# myUZE_final.net
KiCad netlist of a schematic drawn in EAGLE
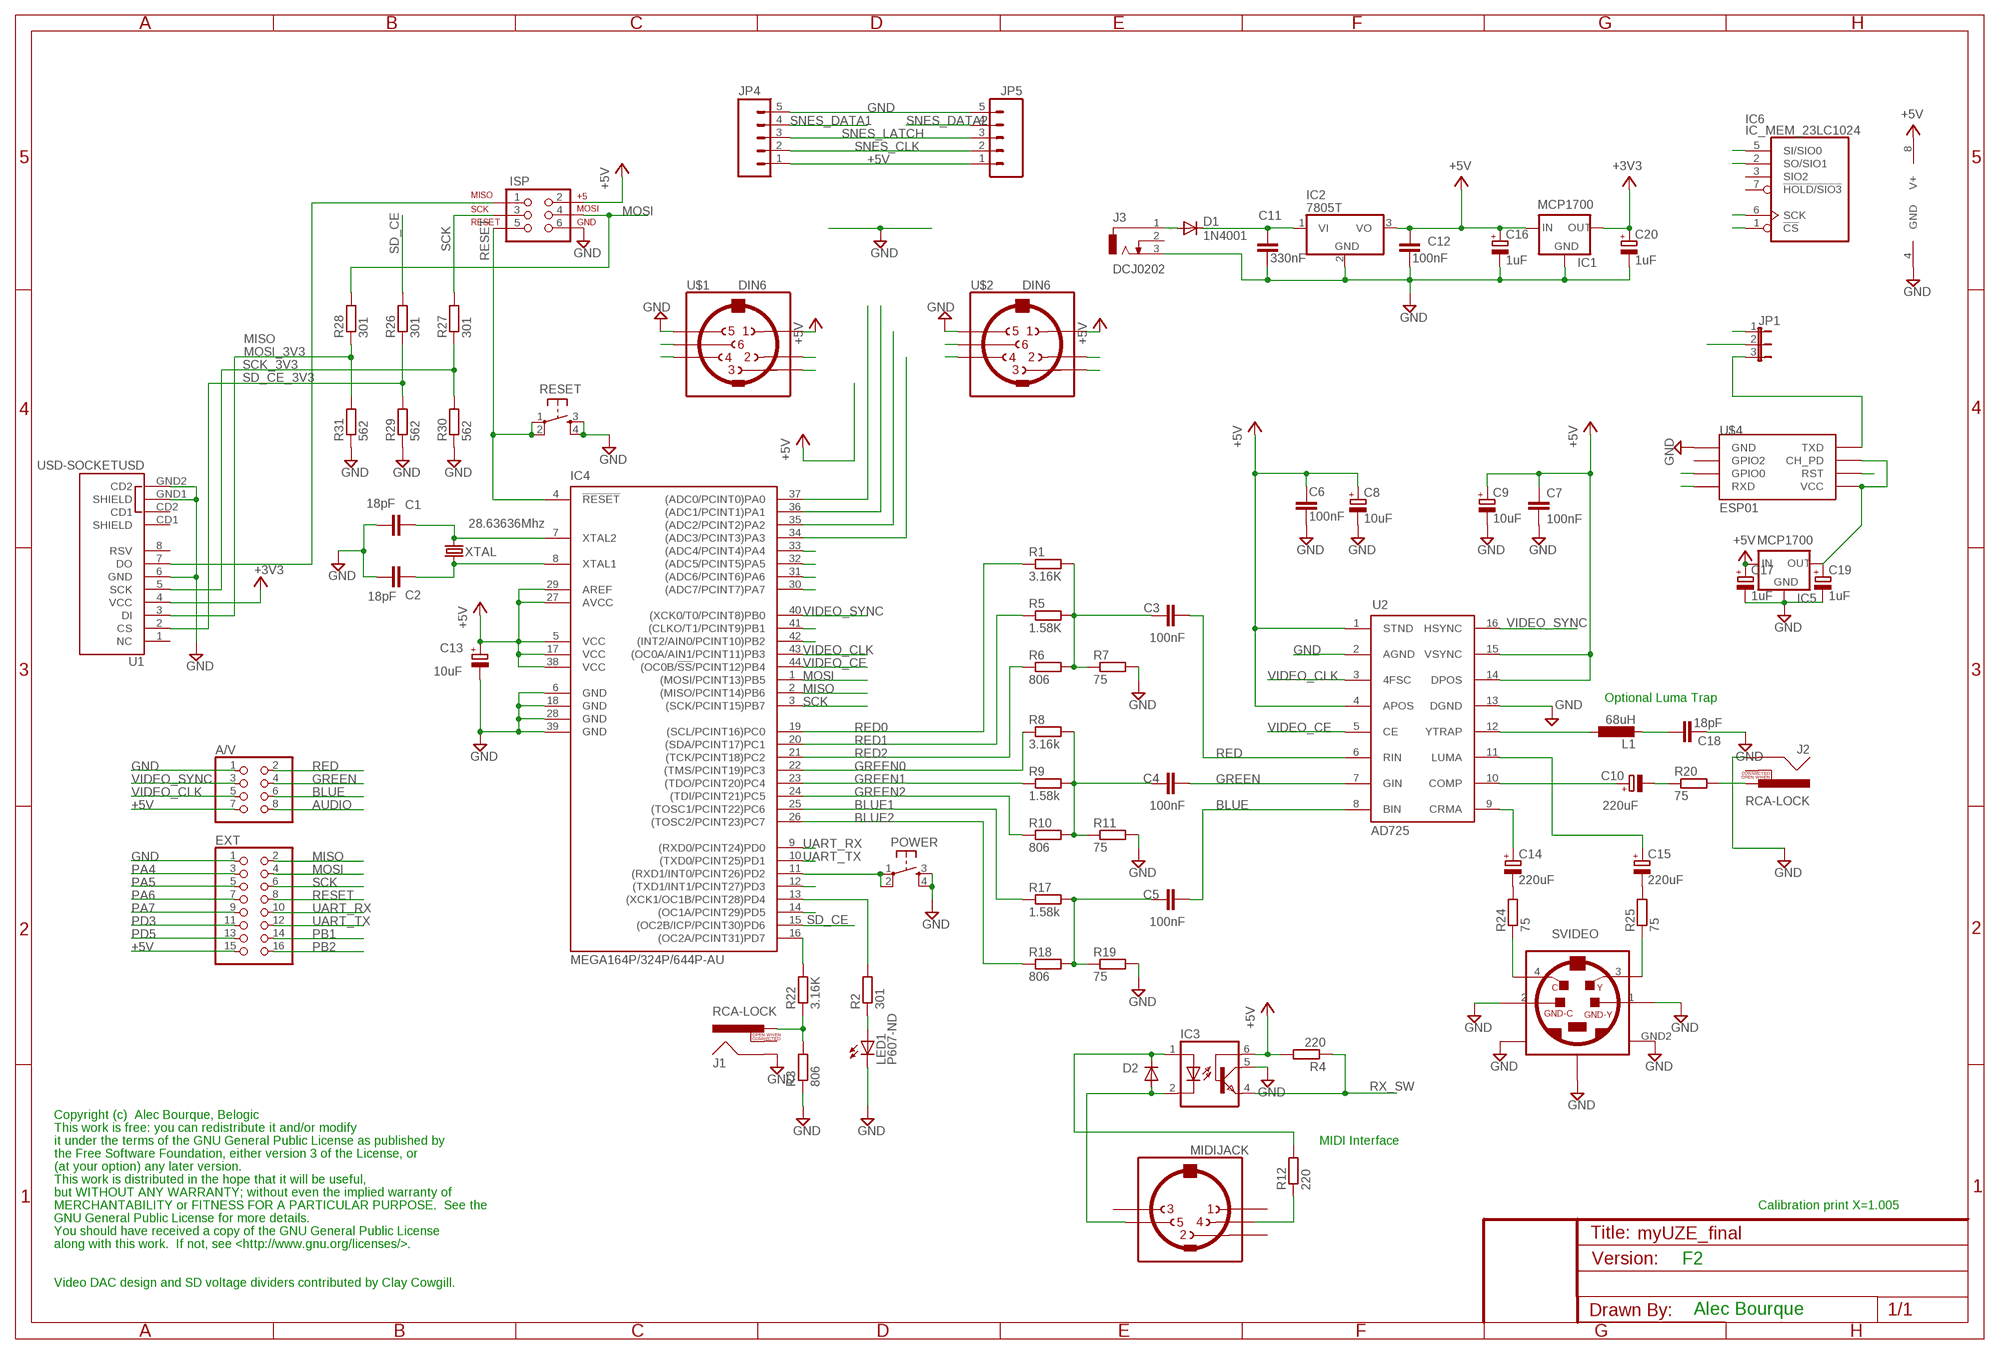
[diagram p0: schematic, sheet 1]

(export (version "E")
  (design (tool "Eeschema 10.0.6"))
  (components
    (comp (ref "A/V")
      (value "PINHD-2X4")
      (footprint "eagle-import:2X04")
      (libsource (lib "eagle-import") (part "PINHD-2X4"))
    )
    (comp (ref "AD725")
      (value "AD725")
      (footprint "eagle-import:SO16W")
      (fields (field (name "IC_NO") "U2") (field (name "NAME") "AD725"))
      (libsource (lib "eagle-import") (part "AD725"))
    )
    (comp (ref "C1")
      (value "18pF")
      (footprint "eagle-import:C0805")
      (libsource (lib "eagle-import") (part "C-EUC0805"))
    )
    (comp (ref "C2")
      (value "18pF")
      (footprint "eagle-import:C0805")
      (libsource (lib "eagle-import") (part "C-EUC0805"))
    )
    (comp (ref "C3")
      (value "100nF")
      (footprint "eagle-import:C0805")
      (libsource (lib "eagle-import") (part "C-EUC0805"))
    )
    (comp (ref "C4")
      (value "100nF")
      (footprint "eagle-import:C0805")
      (libsource (lib "eagle-import") (part "C-EUC0805"))
    )
    (comp (ref "C5")
      (value "100nF")
      (footprint "eagle-import:C0805")
      (libsource (lib "eagle-import") (part "C-EUC0805"))
    )
    (comp (ref "C6")
      (value "100nF")
      (footprint "eagle-import:C0805")
      (libsource (lib "eagle-import") (part "C-EUC0805"))
    )
    (comp (ref "C7")
      (value "100nF")
      (footprint "eagle-import:C0805")
      (libsource (lib "eagle-import") (part "C-EUC0805"))
    )
    (comp (ref "C8")
      (value "10uF")
      (footprint "eagle-import:153CLV-0505")
      (libsource (lib "eagle-import") (part "CPOL-EU153CLV-0505"))
    )
    (comp (ref "C9")
      (value "10uF")
      (footprint "eagle-import:153CLV-0505")
      (libsource (lib "eagle-import") (part "CPOL-EU153CLV-0505"))
    )
    (comp (ref "C10")
      (value "220uF")
      (footprint "eagle-import:E2-5")
      (libsource (lib "eagle-import") (part "CPOL-EUE2-5"))
    )
    (comp (ref "C11")
      (value "330nF")
      (footprint "eagle-import:C0805")
      (libsource (lib "eagle-import") (part "C-EUC0805"))
    )
    (comp (ref "C12")
      (value "100nF")
      (footprint "eagle-import:C0805")
      (libsource (lib "eagle-import") (part "C-EUC0805"))
    )
    (comp (ref "C13")
      (value "10uF")
      (footprint "eagle-import:153CLV-0505")
      (libsource (lib "eagle-import") (part "CPOL-EU153CLV-0505"))
    )
    (comp (ref "C14")
      (value "220uF")
      (footprint "eagle-import:E2-5")
      (libsource (lib "eagle-import") (part "CPOL-EUE2-5"))
    )
    (comp (ref "C15")
      (value "220uF")
      (footprint "eagle-import:E2-5")
      (libsource (lib "eagle-import") (part "CPOL-EUE2-5"))
    )
    (comp (ref "C16")
      (value "1uF")
      (footprint "eagle-import:153CLV-0505")
      (libsource (lib "eagle-import") (part "CPOL-EU153CLV-0505"))
    )
    (comp (ref "C17")
      (value "1uF")
      (footprint "eagle-import:153CLV-0505")
      (libsource (lib "eagle-import") (part "CPOL-EU153CLV-0505"))
    )
    (comp (ref "C18")
      (value "18pF")
      (footprint "eagle-import:C0805")
      (libsource (lib "eagle-import") (part "C-EUC0805"))
    )
    (comp (ref "C19")
      (value "1uF")
      (footprint "eagle-import:153CLV-0505")
      (libsource (lib "eagle-import") (part "CPOL-EU153CLV-0505"))
    )
    (comp (ref "C20")
      (value "1uF")
      (footprint "eagle-import:153CLV-0505")
      (libsource (lib "eagle-import") (part "CPOL-EU153CLV-0505"))
    )
    (comp (ref "D1")
      (value "1N4001")
      (footprint "eagle-import:MELF-MLL41")
      (libsource (lib "eagle-import") (part "DIODE-MELF-MLL41"))
    )
    (comp (ref "D2")
      (value "DIODE-MINIMELF")
      (footprint "eagle-import:MINIMELF")
      (libsource (lib "eagle-import") (part "DIODE-MINIMELF"))
    )
    (comp (ref "EXT")
      (value "PINHD-2X8")
      (footprint "eagle-import:2X08")
      (libsource (lib "eagle-import") (part "PINHD-2X8"))
    )
    (comp (ref "IC1")
      (value "MCP1700")
      (footprint "eagle-import:TO92-INLINE")
      (libsource (lib "eagle-import") (part "MCP1700INLINE"))
    )
    (comp (ref "IC2")
      (value "7805T")
      (footprint "eagle-import:TO220H")
      (libsource (lib "eagle-import") (part "78T05"))
    )
    (comp (ref "IC3")
      (value "PC110")
      (footprint "eagle-import:DIL06")
      (libsource (lib "eagle-import") (part "PC110"))
    )
    (comp (ref "IC4")
      (value "MEGA164P/324P/644P-AU")
      (footprint "eagle-import:TQFP44")
      (libsource (lib "eagle-import") (part "MEGA164P/324P/644P-AU"))
    )
    (comp (ref "IC5")
      (value "MCP1700")
      (footprint "eagle-import:TO92-INLINE")
      (libsource (lib "eagle-import") (part "MCP1700INLINE"))
    )
    (comp (ref "IC6")
      (value "IC_MEM_23LC1024")
      (footprint "eagle-import:SOIC-8")
      (libsource (lib "eagle-import") (part "IC_MEM_23LC1024"))
    )
    (comp (ref "ISP")
      (value "AVR_SPI_PRG_6PTH")
      (footprint "eagle-import:2X3")
      (libsource (lib "eagle-import") (part "AVR_SPI_PRG_6PTH"))
    )
    (comp (ref "J1")
      (value "RCA-LOCK")
      (footprint "eagle-import:RCA_LOCK")
      (libsource (lib "eagle-import") (part "RCA-LOCK"))
    )
    (comp (ref "J2")
      (value "RCA-LOCK")
      (footprint "eagle-import:RCA_LOCK")
      (libsource (lib "eagle-import") (part "RCA-LOCK"))
    )
    (comp (ref "J3")
      (value "DCJ0202")
      (footprint "eagle-import:DCJ0202")
      (libsource (lib "eagle-import") (part "DCJ0202"))
    )
    (comp (ref "JP1")
      (value "JP2E")
      (footprint "eagle-import:JP2")
      (libsource (lib "eagle-import") (part "JP2E"))
    )
    (comp (ref "JP4")
      (value "M05PTH")
      (footprint "eagle-import:1X05")
      (libsource (lib "eagle-import") (part "M05PTH"))
    )
    (comp (ref "JP5")
      (value "M05PTH")
      (footprint "eagle-import:1X05")
      (libsource (lib "eagle-import") (part "M05PTH"))
    )
    (comp (ref "L1")
      (value "68uH")
      (footprint "eagle-import:IR-4")
      (libsource (lib "eagle-import") (part "L-EUIR-4"))
    )
    (comp (ref "LED1")
      (value "P607-ND")
      (footprint "eagle-import:Q62902-B155")
      (libsource (lib "eagle-import") (part "LEDB155"))
    )
    (comp (ref "POWER")
      (value "USER")
      (footprint "eagle-import:TACTILE-PTH")
      (libsource (lib "eagle-import") (part "TAC_SWITCHPTH"))
    )
    (comp (ref "R1")
      (value "3.16K")
      (footprint "eagle-import:R0805")
      (libsource (lib "eagle-import") (part "R-EU_R0805"))
    )
    (comp (ref "R2")
      (value "301")
      (footprint "eagle-import:R0805")
      (libsource (lib "eagle-import") (part "R-EU_R0805"))
    )
    (comp (ref "R3")
      (value "806")
      (footprint "eagle-import:R0805")
      (libsource (lib "eagle-import") (part "R-EU_R0805"))
    )
    (comp (ref "R4")
      (value "220")
      (footprint "eagle-import:R0805")
      (libsource (lib "eagle-import") (part "R-EU_R0805"))
    )
    (comp (ref "R5")
      (value "1.58K")
      (footprint "eagle-import:R0805")
      (libsource (lib "eagle-import") (part "R-EU_R0805"))
    )
    (comp (ref "R6")
      (value "806")
      (footprint "eagle-import:R0805")
      (libsource (lib "eagle-import") (part "R-EU_R0805"))
    )
    (comp (ref "R7")
      (value "75")
      (footprint "eagle-import:R0805")
      (libsource (lib "eagle-import") (part "R-EU_R0805"))
    )
    (comp (ref "R8")
      (value "3.16k")
      (footprint "eagle-import:R0805")
      (libsource (lib "eagle-import") (part "R-EU_R0805"))
    )
    (comp (ref "R9")
      (value "1.58k")
      (footprint "eagle-import:R0805")
      (libsource (lib "eagle-import") (part "R-EU_R0805"))
    )
    (comp (ref "R10")
      (value "806")
      (footprint "eagle-import:R0805")
      (libsource (lib "eagle-import") (part "R-EU_R0805"))
    )
    (comp (ref "R11")
      (value "75")
      (footprint "eagle-import:R0805")
      (libsource (lib "eagle-import") (part "R-EU_R0805"))
    )
    (comp (ref "R12")
      (value "220")
      (footprint "eagle-import:R0805")
      (libsource (lib "eagle-import") (part "R-EU_R0805"))
    )
    (comp (ref "R17")
      (value "1.58k")
      (footprint "eagle-import:R0805")
      (libsource (lib "eagle-import") (part "R-EU_R0805"))
    )
    (comp (ref "R18")
      (value "806")
      (footprint "eagle-import:R0805")
      (libsource (lib "eagle-import") (part "R-EU_R0805"))
    )
    (comp (ref "R19")
      (value "75")
      (footprint "eagle-import:R0805")
      (libsource (lib "eagle-import") (part "R-EU_R0805"))
    )
    (comp (ref "R20")
      (value "75")
      (footprint "eagle-import:R0805")
      (libsource (lib "eagle-import") (part "R-EU_R0805"))
    )
    (comp (ref "R22")
      (value "3.16K")
      (footprint "eagle-import:R0805")
      (libsource (lib "eagle-import") (part "R-EU_R0805"))
    )
    (comp (ref "R24")
      (value "75")
      (footprint "eagle-import:R0805")
      (libsource (lib "eagle-import") (part "R-EU_R0805"))
    )
    (comp (ref "R25")
      (value "75")
      (footprint "eagle-import:R0805")
      (libsource (lib "eagle-import") (part "R-EU_R0805"))
    )
    (comp (ref "R26")
      (value "301")
      (footprint "eagle-import:R0805")
      (libsource (lib "eagle-import") (part "R-EU_R0805"))
    )
    (comp (ref "R27")
      (value "301")
      (footprint "eagle-import:R0805")
      (libsource (lib "eagle-import") (part "R-EU_R0805"))
    )
    (comp (ref "R28")
      (value "301")
      (footprint "eagle-import:R0805")
      (libsource (lib "eagle-import") (part "R-EU_R0805"))
    )
    (comp (ref "R29")
      (value "562")
      (footprint "eagle-import:R0805")
      (libsource (lib "eagle-import") (part "R-EU_R0805"))
    )
    (comp (ref "R30")
      (value "562")
      (footprint "eagle-import:R0805")
      (libsource (lib "eagle-import") (part "R-EU_R0805"))
    )
    (comp (ref "R31")
      (value "562")
      (footprint "eagle-import:R0805")
      (libsource (lib "eagle-import") (part "R-EU_R0805"))
    )
    (comp (ref "RESET")
      (value "RESET")
      (footprint "eagle-import:TACTILE-PTH")
      (libsource (lib "eagle-import") (part "TAC_SWITCHPTH"))
    )
    (comp (ref "SVIDEO")
      (value "S-VIDEO OUT")
      (footprint "eagle-import:MINIDIN4")
      (libsource (lib "eagle-import") (part "MINIDIN"))
    )
    (comp (ref "U$1")
      (value "DIN6")
      (footprint "eagle-import:DIN6")
      (libsource (lib "eagle-import") (part "DIN6"))
    )
    (comp (ref "U$2")
      (value "DIN6")
      (footprint "eagle-import:DIN6")
      (libsource (lib "eagle-import") (part "DIN6"))
    )
    (comp (ref "U$4")
      (value "ESP01")
      (footprint "eagle-import:ESP01")
      (libsource (lib "eagle-import") (part "ESP01"))
    )
    (comp (ref "U$5")
      (value "MIDIJACK")
      (footprint "eagle-import:CP-2350")
      (libsource (lib "eagle-import") (part "MIDIJACK"))
    )
    (comp (ref "U1")
      (value "USD-SOCKETUSD")
      (footprint "eagle-import:USD-SOCKET-PP")
      (libsource (lib "eagle-import") (part "USD-SOCKETUSD"))
    )
    (comp (ref "XTAL")
      (value "28.63636Mhz")
      (footprint "eagle-import:HC49_S")
      (libsource (lib "eagle-import") (part "CRYSTALHC49S"))
    )
  )
  (nets
    (net (code "1") (name "+3V3") (class "Default")
      (node (ref "C20") (pin "+") (pinfunction "+_+") (pintype "passive"))
      (node (ref "IC1") (pin "3") (pinfunction "OUT_3") (pintype "passive"))
      (node (ref "U1") (pin "4") (pinfunction "VCC_4") (pintype "bidirectional"))
    )
    (net (code "2") (name "+5V") (class "Default")
      (node (ref "A/V") (pin "7") (pinfunction "7_7") (pintype "passive"))
      (node (ref "AD725") (pin "1") (pinfunction "STND_1") (pintype "input"))
      (node (ref "AD725") (pin "14") (pinfunction "DPOS_14") (pintype "power_in"))
      (node (ref "AD725") (pin "15") (pinfunction "VSYNC_15") (pintype "input"))
      (node (ref "AD725") (pin "4") (pinfunction "APOS_4") (pintype "power_in"))
      (node (ref "C12") (pin "1") (pinfunction "1_1") (pintype "passive"))
      (node (ref "C13") (pin "+") (pinfunction "+_+") (pintype "passive"))
      (node (ref "C16") (pin "+") (pinfunction "+_+") (pintype "passive"))
      (node (ref "C17") (pin "+") (pinfunction "+_+") (pintype "passive"))
      (node (ref "C6") (pin "1") (pinfunction "1_1") (pintype "passive"))
      (node (ref "C7") (pin "1") (pinfunction "1_1") (pintype "passive"))
      (node (ref "C8") (pin "+") (pinfunction "+_+") (pintype "passive"))
      (node (ref "C9") (pin "+") (pinfunction "+_+") (pintype "passive"))
      (node (ref "EXT") (pin "15") (pinfunction "15_15") (pintype "passive"))
      (node (ref "IC1") (pin "2") (pinfunction "IN_2") (pintype "input"))
      (node (ref "IC2") (pin "3") (pinfunction "VO_3") (pintype "passive"))
      (node (ref "IC3") (pin "6") (pinfunction "BAS_6") (pintype "passive"))
      (node (ref "IC4") (pin "17") (pinfunction "VCC_17") (pintype "power_in"))
      (node (ref "IC4") (pin "27") (pinfunction "AVCC_27") (pintype "power_in"))
      (node (ref "IC4") (pin "29") (pinfunction "AREF_29") (pintype "power_in"))
      (node (ref "IC4") (pin "38") (pinfunction "VCC_38") (pintype "power_in"))
      (node (ref "IC4") (pin "5") (pinfunction "VCC_5") (pintype "power_in"))
      (node (ref "IC5") (pin "2") (pinfunction "IN_2") (pintype "input"))
      (node (ref "IC6") (pin "8") (pinfunction "V+_8") (pintype "power_in"))
      (node (ref "ISP") (pin "2") (pinfunction "2_2") (pintype "passive"))
      (node (ref "JP4") (pin "1") (pinfunction "1_1") (pintype "passive"))
      (node (ref "JP5") (pin "1") (pinfunction "1_1") (pintype "passive"))
      (node (ref "R4") (pin "2") (pinfunction "2_2") (pintype "passive"))
      (node (ref "U$1") (pin "P1") (pinfunction "P1_P1") (pintype "passive"))
      (node (ref "U$2") (pin "P1") (pinfunction "P1_P1") (pintype "passive"))
    )
    (net (code "3") (name "/AUDIO") (class "Default")
      (node (ref "A/V") (pin "8") (pinfunction "8_8") (pintype "passive"))
      (node (ref "J1") (pin "PIN") (pinfunction "PIN_PIN") (pintype "bidirectional"))
      (node (ref "R22") (pin "1") (pinfunction "1_1") (pintype "passive"))
      (node (ref "R3") (pin "2") (pinfunction "2_2") (pintype "passive"))
    )
    (net (code "4") (name "/BLUE") (class "Default")
      (node (ref "A/V") (pin "6") (pinfunction "6_6") (pintype "passive"))
      (node (ref "AD725") (pin "8") (pinfunction "BIN_8") (pintype "input"))
      (node (ref "C5") (pin "2") (pinfunction "2_2") (pintype "passive"))
    )
    (net (code "5") (name "/BLUE1") (class "Default")
      (node (ref "IC4") (pin "25") (pinfunction "(TOSC1/PCINT22)PC6_25") (pintype "bidirectional"))
      (node (ref "R17") (pin "1") (pinfunction "1_1") (pintype "passive"))
    )
    (net (code "6") (name "/BLUE2") (class "Default")
      (node (ref "IC4") (pin "26") (pinfunction "(TOSC2/PCINT23)PC7_26") (pintype "bidirectional"))
      (node (ref "R18") (pin "1") (pinfunction "1_1") (pintype "passive"))
    )
    (net (code "7") (name "/GREEN") (class "Default")
      (node (ref "A/V") (pin "4") (pinfunction "4_4") (pintype "passive"))
      (node (ref "AD725") (pin "7") (pinfunction "GIN_7") (pintype "input"))
      (node (ref "C4") (pin "2") (pinfunction "2_2") (pintype "passive"))
    )
    (net (code "8") (name "/GREEN0") (class "Default")
      (node (ref "IC4") (pin "22") (pinfunction "(TMS/PCINT19)PC3_22") (pintype "bidirectional"))
      (node (ref "R8") (pin "1") (pinfunction "1_1") (pintype "passive"))
    )
    (net (code "9") (name "/GREEN1") (class "Default")
      (node (ref "IC4") (pin "23") (pinfunction "(TDO/PCINT20)PC4_23") (pintype "bidirectional"))
      (node (ref "R9") (pin "1") (pinfunction "1_1") (pintype "passive"))
    )
    (net (code "10") (name "/GREEN2") (class "Default")
      (node (ref "IC4") (pin "24") (pinfunction "(TDI/PCINT21)PC5_24") (pintype "bidirectional"))
      (node (ref "R10") (pin "1") (pinfunction "1_1") (pintype "passive"))
    )
    (net (code "11") (name "/MISO") (class "Default")
      (node (ref "EXT") (pin "2") (pinfunction "2_2") (pintype "passive"))
      (node (ref "IC4") (pin "2") (pinfunction "(MISO/PCINT14)PB6_2") (pintype "bidirectional"))
      (node (ref "IC6") (pin "2") (pinfunction "SO/SIO1_2") (pintype "bidirectional"))
      (node (ref "ISP") (pin "1") (pinfunction "1_1") (pintype "passive"))
      (node (ref "U1") (pin "7") (pinfunction "DO_7") (pintype "bidirectional"))
    )
    (net (code "12") (name "/MOSI") (class "Default")
      (node (ref "EXT") (pin "4") (pinfunction "4_4") (pintype "passive"))
      (node (ref "IC4") (pin "1") (pinfunction "(MOSI/PCINT13)PB5_1") (pintype "bidirectional"))
      (node (ref "IC6") (pin "5") (pinfunction "SI/SIO0_5") (pintype "bidirectional"))
      (node (ref "ISP") (pin "4") (pinfunction "4_4") (pintype "passive"))
      (node (ref "R28") (pin "2") (pinfunction "2_2") (pintype "passive"))
    )
    (net (code "13") (name "/MOSI_3V3") (class "Default")
      (node (ref "R28") (pin "1") (pinfunction "1_1") (pintype "passive"))
      (node (ref "R31") (pin "2") (pinfunction "2_2") (pintype "passive"))
      (node (ref "U1") (pin "3") (pinfunction "DI_3") (pintype "bidirectional"))
    )
    (net (code "14") (name "/PA4") (class "Default")
      (node (ref "EXT") (pin "3") (pinfunction "3_3") (pintype "passive"))
      (node (ref "IC4") (pin "33") (pinfunction "(ADC4/PCINT4)PA4_33") (pintype "bidirectional"))
      (node (ref "IC6") (pin "1") (pinfunction "~{CS}_1") (pintype "input"))
    )
    (net (code "15") (name "/PA5") (class "Default")
      (node (ref "EXT") (pin "5") (pinfunction "5_5") (pintype "passive"))
      (node (ref "IC4") (pin "32") (pinfunction "(ADC5/PCINT5)PA5_32") (pintype "bidirectional"))
    )
    (net (code "16") (name "/PA6") (class "Default")
      (node (ref "EXT") (pin "7") (pinfunction "7_7") (pintype "passive"))
      (node (ref "IC4") (pin "31") (pinfunction "(ADC6/PCINT6)PA6_31") (pintype "bidirectional"))
    )
    (net (code "17") (name "/PA7") (class "Default")
      (node (ref "EXT") (pin "9") (pinfunction "9_9") (pintype "passive"))
      (node (ref "IC4") (pin "30") (pinfunction "(ADC7/PCINT7)PA7_30") (pintype "bidirectional"))
      (node (ref "U$4") (pin "GPIO0") (pinfunction "GPIO0_GPIO0") (pintype "bidirectional"))
    )
    (net (code "18") (name "/PB1") (class "Default")
      (node (ref "EXT") (pin "14") (pinfunction "14_14") (pintype "passive"))
      (node (ref "IC4") (pin "41") (pinfunction "(CLKO/T1/PCINT9)PB1_41") (pintype "bidirectional"))
    )
    (net (code "19") (name "/PB2") (class "Default")
      (node (ref "EXT") (pin "16") (pinfunction "16_16") (pintype "passive"))
      (node (ref "IC4") (pin "42") (pinfunction "(INT2/AIN0/PCINT10)PB2_42") (pintype "bidirectional"))
    )
    (net (code "20") (name "/PD3") (class "Default")
      (node (ref "EXT") (pin "11") (pinfunction "11_11") (pintype "passive"))
      (node (ref "IC4") (pin "12") (pinfunction "(TXD1/INT1/PCINT27)PD3_12") (pintype "bidirectional"))
      (node (ref "U$4") (pin "RST") (pinfunction "RST_RST") (pintype "bidirectional"))
    )
    (net (code "21") (name "/PD5") (class "Default")
      (node (ref "EXT") (pin "13") (pinfunction "13_13") (pintype "passive"))
      (node (ref "IC4") (pin "14") (pinfunction "(OC1A/PCINT29)PD5_14") (pintype "bidirectional"))
    )
    (net (code "22") (name "/RED") (class "Default")
      (node (ref "A/V") (pin "2") (pinfunction "2_2") (pintype "passive"))
      (node (ref "AD725") (pin "6") (pinfunction "RIN_6") (pintype "input"))
      (node (ref "C3") (pin "2") (pinfunction "2_2") (pintype "passive"))
    )
    (net (code "23") (name "/RED0") (class "Default")
      (node (ref "IC4") (pin "19") (pinfunction "(SCL/PCINT16)PC0_19") (pintype "bidirectional"))
      (node (ref "R1") (pin "1") (pinfunction "1_1") (pintype "passive"))
    )
    (net (code "24") (name "/RED1") (class "Default")
      (node (ref "IC4") (pin "20") (pinfunction "(SDA/PCINT17)PC1_20") (pintype "bidirectional"))
      (node (ref "R5") (pin "1") (pinfunction "1_1") (pintype "passive"))
    )
    (net (code "25") (name "/RED2") (class "Default")
      (node (ref "IC4") (pin "21") (pinfunction "(TCK/PCINT18)PC2_21") (pintype "bidirectional"))
      (node (ref "R6") (pin "1") (pinfunction "1_1") (pintype "passive"))
    )
    (net (code "26") (name "/RESET") (class "Default")
      (node (ref "EXT") (pin "8") (pinfunction "8_8") (pintype "passive"))
      (node (ref "IC4") (pin "4") (pinfunction "~{RESET}_4") (pintype "input"))
      (node (ref "ISP") (pin "5") (pinfunction "5_5") (pintype "passive"))
      (node (ref "RESET") (pin "1") (pinfunction "1_1") (pintype "passive"))
      (node (ref "RESET") (pin "2") (pinfunction "2_2") (pintype "passive"))
    )
    (net (code "27") (name "/RX_SW") (class "Default")
      (node (ref "IC3") (pin "4") (pinfunction "EMI_4") (pintype "passive"))
      (node (ref "JP1") (pin "1") (pinfunction "1_1") (pintype "passive"))
      (node (ref "R4") (pin "1") (pinfunction "1_1") (pintype "passive"))
    )
    (net (code "28") (name "/SCK") (class "Default")
      (node (ref "EXT") (pin "6") (pinfunction "6_6") (pintype "passive"))
      (node (ref "IC4") (pin "3") (pinfunction "(SCK/PCINT15)PB7_3") (pintype "bidirectional"))
      (node (ref "IC6") (pin "6") (pinfunction "SCK_6") (pintype "input"))
      (node (ref "ISP") (pin "3") (pinfunction "3_3") (pintype "passive"))
      (node (ref "R27") (pin "2") (pinfunction "2_2") (pintype "passive"))
    )
    (net (code "29") (name "/SCK_3V3") (class "Default")
      (node (ref "R27") (pin "1") (pinfunction "1_1") (pintype "passive"))
      (node (ref "R30") (pin "2") (pinfunction "2_2") (pintype "passive"))
      (node (ref "U1") (pin "5") (pinfunction "SCK_5") (pintype "bidirectional"))
    )
    (net (code "30") (name "/SD_CE") (class "Default")
      (node (ref "IC4") (pin "15") (pinfunction "(OC2B/ICP/PCINT30)PD6_15") (pintype "bidirectional"))
      (node (ref "R26") (pin "2") (pinfunction "2_2") (pintype "passive"))
    )
    (net (code "31") (name "/SD_CE_3V3") (class "Default")
      (node (ref "R26") (pin "1") (pinfunction "1_1") (pintype "passive"))
      (node (ref "R29") (pin "2") (pinfunction "2_2") (pintype "passive"))
      (node (ref "U1") (pin "2") (pinfunction "CS_2") (pintype "bidirectional"))
    )
    (net (code "32") (name "/SNES_CLK") (class "Default")
      (node (ref "IC4") (pin "34") (pinfunction "(ADC3/PCINT3)PA3_34") (pintype "bidirectional"))
      (node (ref "JP4") (pin "2") (pinfunction "2_2") (pintype "passive"))
      (node (ref "JP5") (pin "2") (pinfunction "2_2") (pintype "passive"))
      (node (ref "U$1") (pin "P2") (pinfunction "P2_P2") (pintype "passive"))
      (node (ref "U$2") (pin "P2") (pinfunction "P2_P2") (pintype "passive"))
    )
    (net (code "33") (name "/SNES_DATA1") (class "Default")
      (node (ref "IC4") (pin "37") (pinfunction "(ADC0/PCINT0)PA0_37") (pintype "bidirectional"))
      (node (ref "JP4") (pin "4") (pinfunction "4_4") (pintype "passive"))
      (node (ref "U$2") (pin "P4") (pinfunction "P4_P4") (pintype "passive"))
    )
    (net (code "34") (name "/SNES_DATA2") (class "Default")
      (node (ref "IC4") (pin "36") (pinfunction "(ADC1/PCINT1)PA1_36") (pintype "bidirectional"))
      (node (ref "JP5") (pin "4") (pinfunction "4_4") (pintype "passive"))
      (node (ref "U$1") (pin "P4") (pinfunction "P4_P4") (pintype "passive"))
    )
    (net (code "35") (name "/SNES_LATCH") (class "Default")
      (node (ref "IC4") (pin "35") (pinfunction "(ADC2/PCINT2)PA2_35") (pintype "bidirectional"))
      (node (ref "JP4") (pin "3") (pinfunction "3_3") (pintype "passive"))
      (node (ref "JP5") (pin "3") (pinfunction "3_3") (pintype "passive"))
      (node (ref "U$1") (pin "P3") (pinfunction "P3_P3") (pintype "passive"))
      (node (ref "U$2") (pin "P3") (pinfunction "P3_P3") (pintype "passive"))
    )
    (net (code "36") (name "/UART_RX") (class "Default")
      (node (ref "EXT") (pin "10") (pinfunction "10_10") (pintype "passive"))
      (node (ref "IC4") (pin "9") (pinfunction "(RXD0/PCINT24)PD0_9") (pintype "bidirectional"))
      (node (ref "JP1") (pin "2") (pinfunction "2_2") (pintype "passive"))
    )
    (net (code "37") (name "/UART_TX") (class "Default")
      (node (ref "EXT") (pin "12") (pinfunction "12_12") (pintype "passive"))
      (node (ref "IC4") (pin "10") (pinfunction "(TXD0/PCINT25)PD1_10") (pintype "bidirectional"))
      (node (ref "U$4") (pin "RX") (pinfunction "RXD_RX") (pintype "bidirectional"))
    )
    (net (code "38") (name "/VIDEO_CE") (class "Default")
      (node (ref "AD725") (pin "5") (pinfunction "CE_5") (pintype "input"))
      (node (ref "IC4") (pin "44") (pinfunction "(OC0B/~{SS}/PCINT12)PB4_44") (pintype "bidirectional"))
    )
    (net (code "39") (name "/VIDEO_CLK") (class "Default")
      (node (ref "A/V") (pin "5") (pinfunction "5_5") (pintype "passive"))
      (node (ref "AD725") (pin "3") (pinfunction "4FSC_3") (pintype "input"))
      (node (ref "IC4") (pin "43") (pinfunction "(OC0A/AIN1/PCINT11)PB3_43") (pintype "bidirectional"))
    )
    (net (code "40") (name "/VIDEO_SYNC") (class "Default")
      (node (ref "A/V") (pin "3") (pinfunction "3_3") (pintype "passive"))
      (node (ref "AD725") (pin "16") (pinfunction "HSYNC_16") (pintype "input"))
      (node (ref "IC4") (pin "40") (pinfunction "(XCK0/T0/PCINT8)PB0_40") (pintype "bidirectional"))
    )
    (net (code "41") (name "GND") (class "Default")
      (node (ref "A/V") (pin "1") (pinfunction "1_1") (pintype "passive"))
      (node (ref "AD725") (pin "13") (pinfunction "DGND_13") (pintype "passive"))
      (node (ref "AD725") (pin "2") (pinfunction "AGND_2") (pintype "passive"))
      (node (ref "C1") (pin "2") (pinfunction "2_2") (pintype "passive"))
      (node (ref "C11") (pin "2") (pinfunction "2_2") (pintype "passive"))
      (node (ref "C12") (pin "2") (pinfunction "2_2") (pintype "passive"))
      (node (ref "C13") (pin "-") (pinfunction "-_-") (pintype "passive"))
      (node (ref "C16") (pin "-") (pinfunction "-_-") (pintype "passive"))
      (node (ref "C17") (pin "-") (pinfunction "-_-") (pintype "passive"))
      (node (ref "C18") (pin "2") (pinfunction "2_2") (pintype "passive"))
      (node (ref "C19") (pin "-") (pinfunction "-_-") (pintype "passive"))
      (node (ref "C2") (pin "2") (pinfunction "2_2") (pintype "passive"))
      (node (ref "C20") (pin "-") (pinfunction "-_-") (pintype "passive"))
      (node (ref "C6") (pin "2") (pinfunction "2_2") (pintype "passive"))
      (node (ref "C7") (pin "2") (pinfunction "2_2") (pintype "passive"))
      (node (ref "C8") (pin "-") (pinfunction "-_-") (pintype "passive"))
      (node (ref "C9") (pin "-") (pinfunction "-_-") (pintype "passive"))
      (node (ref "EXT") (pin "1") (pinfunction "1_1") (pintype "passive"))
      (node (ref "IC1") (pin "1") (pinfunction "GND_1") (pintype "input"))
      (node (ref "IC2") (pin "2") (pinfunction "GND_2") (pintype "passive"))
      (node (ref "IC3") (pin "5") (pinfunction "COL_5") (pintype "passive"))
      (node (ref "IC4") (pin "18") (pinfunction "GND_18") (pintype "power_in"))
      (node (ref "IC4") (pin "28") (pinfunction "GND_28") (pintype "power_in"))
      (node (ref "IC4") (pin "39") (pinfunction "GND_39") (pintype "power_in"))
      (node (ref "IC4") (pin "6") (pinfunction "GND_6") (pintype "power_in"))
      (node (ref "IC5") (pin "1") (pinfunction "GND_1") (pintype "input"))
      (node (ref "IC6") (pin "4") (pinfunction "GND_4") (pintype "power_in"))
      (node (ref "ISP") (pin "6") (pinfunction "6_6") (pintype "passive"))
      (node (ref "J1") (pin "SHELL") (pinfunction "SHELL_SHELL") (pintype "bidirectional"))
      (node (ref "J2") (pin "SHELL") (pinfunction "SHELL_SHELL") (pintype "bidirectional"))
      (node (ref "J3") (pin "3") (pinfunction "3_3") (pintype "passive"))
      (node (ref "JP4") (pin "5") (pinfunction "5_5") (pintype "passive"))
      (node (ref "JP5") (pin "5") (pinfunction "5_5") (pintype "passive"))
      (node (ref "LED1") (pin "K") (pinfunction "C_K") (pintype "passive"))
      (node (ref "POWER") (pin "3") (pinfunction "3_3") (pintype "passive"))
      (node (ref "POWER") (pin "4") (pinfunction "4_4") (pintype "passive"))
      (node (ref "R11") (pin "2") (pinfunction "2_2") (pintype "passive"))
      (node (ref "R19") (pin "2") (pinfunction "2_2") (pintype "passive"))
      (node (ref "R29") (pin "1") (pinfunction "1_1") (pintype "passive"))
      (node (ref "R3") (pin "1") (pinfunction "1_1") (pintype "passive"))
      (node (ref "R30") (pin "1") (pinfunction "1_1") (pintype "passive"))
      (node (ref "R31") (pin "1") (pinfunction "1_1") (pintype "passive"))
      (node (ref "R7") (pin "2") (pinfunction "2_2") (pintype "passive"))
      (node (ref "RESET") (pin "3") (pinfunction "3_3") (pintype "passive"))
      (node (ref "RESET") (pin "4") (pinfunction "4_4") (pintype "passive"))
      (node (ref "SVIDEO") (pin "1") (pinfunction "GND-Y_1") (pintype "passive"))
      (node (ref "SVIDEO") (pin "2") (pinfunction "GND-C_2") (pintype "passive"))
      (node (ref "SVIDEO") (pin "GND1") (pinfunction "P$5_GND1") (pintype "passive"))
      (node (ref "SVIDEO") (pin "GND2") (pinfunction "P$6_GND2") (pintype "passive"))
      (node (ref "SVIDEO") (pin "GND3") (pinfunction "P$7_GND3") (pintype "passive"))
      (node (ref "U$1") (pin "P5") (pinfunction "P5_P5") (pintype "passive"))
      (node (ref "U$2") (pin "P5") (pinfunction "P5_P5") (pintype "passive"))
      (node (ref "U$4") (pin "GND") (pinfunction "GND_GND") (pintype "bidirectional"))
      (node (ref "U1") (pin "6") (pinfunction "GND_6") (pintype "bidirectional"))
      (node (ref "U1") (pin "GND1") (pinfunction "SHIELD_GND1") (pintype "bidirectional"))
      (node (ref "U1") (pin "GND2") (pinfunction "CD2_GND2") (pintype "bidirectional"))
    )
    (net (code "42") (name "Net-(AD725-COMP)") (class "Default")
      (node (ref "AD725") (pin "10") (pinfunction "COMP_10") (pintype "output"))
      (node (ref "C10") (pin "+") (pinfunction "+_+") (pintype "passive"))
    )
    (net (code "43") (name "Net-(AD725-CRMA)") (class "Default")
      (node (ref "AD725") (pin "9") (pinfunction "CRMA_9") (pintype "output"))
      (node (ref "C14") (pin "+") (pinfunction "+_+") (pintype "passive"))
    )
    (net (code "44") (name "Net-(AD725-LUMA)") (class "Default")
      (node (ref "AD725") (pin "11") (pinfunction "LUMA_11") (pintype "output"))
      (node (ref "C15") (pin "+") (pinfunction "+_+") (pintype "passive"))
    )
    (net (code "45") (name "Net-(AD725-YTRAP)") (class "Default")
      (node (ref "AD725") (pin "12") (pinfunction "YTRAP_12") (pintype "output"))
      (node (ref "L1") (pin "1") (pinfunction "1_1") (pintype "passive"))
    )
    (net (code "46") (name "Net-(C3-Pad1)") (class "Default")
      (node (ref "C3") (pin "1") (pinfunction "1_1") (pintype "passive"))
      (node (ref "R1") (pin "2") (pinfunction "2_2") (pintype "passive"))
      (node (ref "R5") (pin "2") (pinfunction "2_2") (pintype "passive"))
      (node (ref "R6") (pin "2") (pinfunction "2_2") (pintype "passive"))
      (node (ref "R7") (pin "1") (pinfunction "1_1") (pintype "passive"))
    )
    (net (code "47") (name "Net-(C4-Pad1)") (class "Default")
      (node (ref "C4") (pin "1") (pinfunction "1_1") (pintype "passive"))
      (node (ref "R10") (pin "2") (pinfunction "2_2") (pintype "passive"))
      (node (ref "R11") (pin "1") (pinfunction "1_1") (pintype "passive"))
      (node (ref "R8") (pin "2") (pinfunction "2_2") (pintype "passive"))
      (node (ref "R9") (pin "2") (pinfunction "2_2") (pintype "passive"))
    )
    (net (code "48") (name "Net-(C5-Pad1)") (class "Default")
      (node (ref "C5") (pin "1") (pinfunction "1_1") (pintype "passive"))
      (node (ref "R17") (pin "2") (pinfunction "2_2") (pintype "passive"))
      (node (ref "R18") (pin "2") (pinfunction "2_2") (pintype "passive"))
      (node (ref "R19") (pin "1") (pinfunction "1_1") (pintype "passive"))
    )
    (net (code "49") (name "Net-(C10-Pad-)") (class "Default")
      (node (ref "C10") (pin "-") (pinfunction "-_-") (pintype "passive"))
      (node (ref "R20") (pin "1") (pinfunction "1_1") (pintype "passive"))
    )
    (net (code "50") (name "Net-(C14-Pad-)") (class "Default")
      (node (ref "C14") (pin "-") (pinfunction "-_-") (pintype "passive"))
      (node (ref "R24") (pin "2") (pinfunction "2_2") (pintype "passive"))
    )
    (net (code "51") (name "Net-(C15-Pad-)") (class "Default")
      (node (ref "C15") (pin "-") (pinfunction "-_-") (pintype "passive"))
      (node (ref "R25") (pin "2") (pinfunction "2_2") (pintype "passive"))
    )
    (net (code "52") (name "Net-(C18-Pad1)") (class "Default")
      (node (ref "C18") (pin "1") (pinfunction "1_1") (pintype "passive"))
      (node (ref "L1") (pin "2") (pinfunction "2_2") (pintype "passive"))
    )
    (net (code "53") (name "Net-(D1-PadA)") (class "Default")
      (node (ref "D1") (pin "A") (pinfunction "A_A") (pintype "passive"))
      (node (ref "J3") (pin "1") (pinfunction "1_1") (pintype "passive"))
    )
    (net (code "54") (name "Net-(IC2-VI)") (class "Default")
      (node (ref "C11") (pin "1") (pinfunction "1_1") (pintype "passive"))
      (node (ref "D1") (pin "C") (pinfunction "C_C") (pintype "passive"))
      (node (ref "IC2") (pin "1") (pinfunction "VI_1") (pintype "input"))
    )
    (net (code "55") (name "Net-(IC3-A)") (class "Default")
      (node (ref "D2") (pin "C") (pinfunction "C_C") (pintype "passive"))
      (node (ref "IC3") (pin "1") (pinfunction "A_1") (pintype "passive"))
      (node (ref "R12") (pin "2") (pinfunction "2_2") (pintype "passive"))
    )
    (net (code "56") (name "Net-(IC3-C)") (class "Default")
      (node (ref "D2") (pin "A") (pinfunction "A_A") (pintype "passive"))
      (node (ref "IC3") (pin "2") (pinfunction "C_2") (pintype "passive"))
      (node (ref "U$5") (pin "5") (pinfunction "5_5") (pintype "passive"))
    )
    (net (code "57") (name "Net-(IC4-(OC2A{slash}PCINT31)PD7)") (class "Default")
      (node (ref "IC4") (pin "16") (pinfunction "(OC2A/PCINT31)PD7_16") (pintype "bidirectional"))
      (node (ref "R22") (pin "2") (pinfunction "2_2") (pintype "passive"))
    )
    (net (code "58") (name "Net-(IC4-(RXD1{slash}INT0{slash}PCINT26)PD2)") (class "Default")
      (node (ref "IC4") (pin "11") (pinfunction "(RXD1/INT0/PCINT26)PD2_11") (pintype "bidirectional"))
      (node (ref "POWER") (pin "1") (pinfunction "1_1") (pintype "passive"))
      (node (ref "POWER") (pin "2") (pinfunction "2_2") (pintype "passive"))
    )
    (net (code "59") (name "Net-(IC4-(XCK1{slash}OC1B{slash}PCINT28)PD4)") (class "Default")
      (node (ref "IC4") (pin "13") (pinfunction "(XCK1/OC1B/PCINT28)PD4_13") (pintype "bidirectional"))
      (node (ref "R2") (pin "2") (pinfunction "2_2") (pintype "passive"))
    )
    (net (code "60") (name "Net-(IC4-XTAL1)") (class "Default")
      (node (ref "C2") (pin "1") (pinfunction "1_1") (pintype "passive"))
      (node (ref "IC4") (pin "8") (pinfunction "XTAL1_8") (pintype "input"))
      (node (ref "XTAL") (pin "1") (pinfunction "1_1") (pintype "passive"))
    )
    (net (code "61") (name "Net-(IC4-XTAL2)") (class "Default")
      (node (ref "C1") (pin "1") (pinfunction "1_1") (pintype "passive"))
      (node (ref "IC4") (pin "7") (pinfunction "XTAL2_7") (pintype "output"))
      (node (ref "XTAL") (pin "2") (pinfunction "2_2") (pintype "passive"))
    )
    (net (code "62") (name "Net-(IC5-OUT)") (class "Default")
      (node (ref "C19") (pin "+") (pinfunction "+_+") (pintype "passive"))
      (node (ref "IC5") (pin "3") (pinfunction "OUT_3") (pintype "passive"))
      (node (ref "U$4") (pin "CH_PD") (pinfunction "CH_PD_CH_PD") (pintype "bidirectional"))
      (node (ref "U$4") (pin "VCC") (pinfunction "VCC_VCC") (pintype "bidirectional"))
    )
    (net (code "63") (name "Net-(J2-PadPIN)") (class "Default")
      (node (ref "J2") (pin "PIN") (pinfunction "PIN_PIN") (pintype "bidirectional"))
      (node (ref "R20") (pin "2") (pinfunction "2_2") (pintype "passive"))
    )
    (net (code "64") (name "Net-(LED1-PadA)") (class "Default")
      (node (ref "LED1") (pin "A") (pinfunction "A_A") (pintype "passive"))
      (node (ref "R2") (pin "1") (pinfunction "1_1") (pintype "passive"))
    )
    (net (code "65") (name "Net-(R12-Pad1)") (class "Default")
      (node (ref "R12") (pin "1") (pinfunction "1_1") (pintype "passive"))
      (node (ref "U$5") (pin "4") (pinfunction "4_4") (pintype "passive"))
    )
    (net (code "66") (name "Net-(SVIDEO-C)") (class "Default")
      (node (ref "R24") (pin "1") (pinfunction "1_1") (pintype "passive"))
      (node (ref "SVIDEO") (pin "4") (pinfunction "C_4") (pintype "output"))
    )
    (net (code "67") (name "Net-(SVIDEO-Y)") (class "Default")
      (node (ref "R25") (pin "1") (pinfunction "1_1") (pintype "passive"))
      (node (ref "SVIDEO") (pin "3") (pinfunction "Y_3") (pintype "output"))
    )
    (net (code "68") (name "Net-(U$4-TXD)") (class "Default")
      (node (ref "JP1") (pin "3") (pinfunction "3_3") (pintype "passive"))
      (node (ref "U$4") (pin "TX") (pinfunction "TXD_TX") (pintype "bidirectional"))
    )
    (net (code "69") (name "unconnected-(IC6A-SIO2-Pad3)") (class "Default")
      (node (ref "IC6") (pin "3") (pinfunction "SIO2_3") (pintype "bidirectional"))
    )
    (net (code "70") (name "unconnected-(IC6A-~{HOLD{slash}SIO3}-Pad7)") (class "Default")
      (node (ref "IC6") (pin "7") (pinfunction "~{HOLD/SIO3}_7") (pintype "input"))
    )
    (net (code "71") (name "unconnected-(J1-PadSWITCH)") (class "Default")
      (node (ref "J1") (pin "SWITCH") (pinfunction "SWITCH_SWITCH") (pintype "bidirectional"))
    )
    (net (code "72") (name "unconnected-(J2-PadSWITCH)") (class "Default")
      (node (ref "J2") (pin "SWITCH") (pinfunction "SWITCH_SWITCH") (pintype "bidirectional"))
    )
    (net (code "73") (name "unconnected-(J3-Pad2)") (class "Default")
      (node (ref "J3") (pin "2") (pinfunction "2_2") (pintype "passive"))
    )
    (net (code "74") (name "unconnected-(U$1-PadP6)") (class "Default")
      (node (ref "U$1") (pin "P6") (pinfunction "P6_P6") (pintype "passive"))
    )
    (net (code "75") (name "unconnected-(U$2-PadP6)") (class "Default")
      (node (ref "U$2") (pin "P6") (pinfunction "P6_P6") (pintype "passive"))
    )
    (net (code "76") (name "unconnected-(U$4-PadGPIO2)") (class "Default")
      (node (ref "U$4") (pin "GPIO2") (pinfunction "GPIO2_GPIO2") (pintype "bidirectional"))
    )
    (net (code "77") (name "unconnected-(U$5-Pad1)") (class "Default")
      (node (ref "U$5") (pin "1") (pinfunction "1_1") (pintype "passive"))
    )
    (net (code "78") (name "unconnected-(U$5-Pad2)") (class "Default")
      (node (ref "U$5") (pin "2") (pinfunction "2_2") (pintype "passive"))
    )
    (net (code "79") (name "unconnected-(U$5-Pad3)") (class "Default")
      (node (ref "U$5") (pin "3") (pinfunction "3_3") (pintype "passive"))
    )
    (net (code "80") (name "unconnected-(U1-CD1-PadCD2)") (class "Default")
      (node (ref "U1") (pin "CD2") (pinfunction "CD1_CD2") (pintype "bidirectional"))
    )
    (net (code "81") (name "unconnected-(U1-NC-Pad1)") (class "Default")
      (node (ref "U1") (pin "1") (pinfunction "NC_1") (pintype "bidirectional"))
    )
    (net (code "82") (name "unconnected-(U1-RSV-Pad8)") (class "Default")
      (node (ref "U1") (pin "8") (pinfunction "RSV_8") (pintype "bidirectional"))
    )
    (net (code "83") (name "unconnected-(U1-SHIELD-PadCD1)") (class "Default")
      (node (ref "U1") (pin "CD1") (pinfunction "SHIELD_CD1") (pintype "bidirectional"))
    )
  )
)
